# untitled.net
KiCad netlist of a schematic drawn in EAGLE
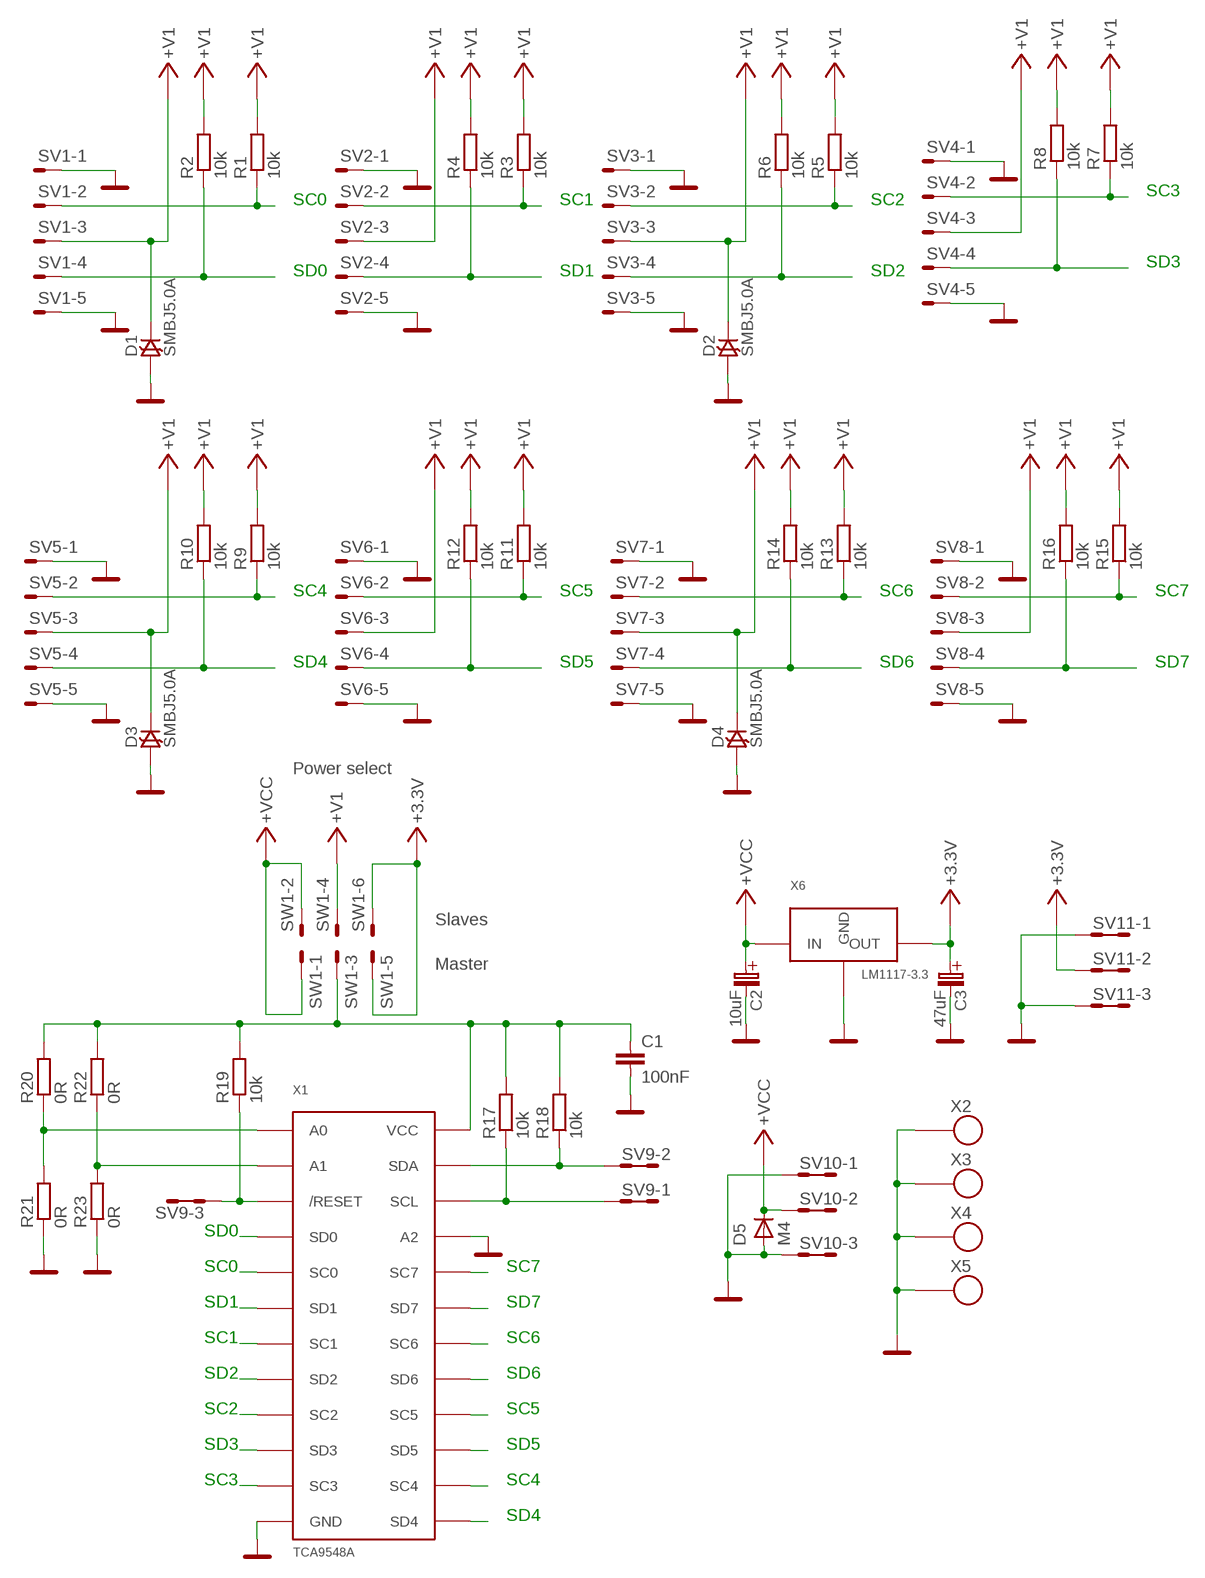
[diagram p0: schematic, sheet 1]

(export (version "E")
  (design (tool "Eeschema 10.0.6"))
  (components
    (comp (ref "C1")
      (value "100nF")
      (footprint "eagle-import:C0805")
      (libsource (lib "eagle-import") (part "C0805"))
    )
    (comp (ref "C2") (value "10uF") (footprint "eagle-import:B") (libsource (lib "eagle-import") (part "B")))
    (comp (ref "C3") (value "47uF") (footprint "eagle-import:C") (libsource (lib "eagle-import") (part "C")))
    (comp (ref "D1")
      (value "SMBJ5.0A")
      (footprint "eagle-import:SMA")
      (libsource (lib "eagle-import") (part "D-TRANSIL-SMA"))
    )
    (comp (ref "D2")
      (value "SMBJ5.0A")
      (footprint "eagle-import:SMA")
      (libsource (lib "eagle-import") (part "D-TRANSIL-SMA"))
    )
    (comp (ref "D3")
      (value "SMBJ5.0A")
      (footprint "eagle-import:SMA")
      (libsource (lib "eagle-import") (part "D-TRANSIL-SMA"))
    )
    (comp (ref "D4")
      (value "SMBJ5.0A")
      (footprint "eagle-import:SMA")
      (libsource (lib "eagle-import") (part "D-TRANSIL-SMA"))
    )
    (comp (ref "D5")
      (value "M4")
      (footprint "eagle-import:SMA")
      (libsource (lib "eagle-import") (part "D-OB.SMA"))
    )
    (comp (ref "R1")
      (value "10k")
      (footprint "eagle-import:0805")
      (libsource (lib "eagle-import") (part "R0805"))
    )
    (comp (ref "R2")
      (value "10k")
      (footprint "eagle-import:0805")
      (libsource (lib "eagle-import") (part "R0805"))
    )
    (comp (ref "R3")
      (value "10k")
      (footprint "eagle-import:0805")
      (libsource (lib "eagle-import") (part "R0805"))
    )
    (comp (ref "R4")
      (value "10k")
      (footprint "eagle-import:0805")
      (libsource (lib "eagle-import") (part "R0805"))
    )
    (comp (ref "R5")
      (value "10k")
      (footprint "eagle-import:0805")
      (libsource (lib "eagle-import") (part "R0805"))
    )
    (comp (ref "R6")
      (value "10k")
      (footprint "eagle-import:0805")
      (libsource (lib "eagle-import") (part "R0805"))
    )
    (comp (ref "R7")
      (value "10k")
      (footprint "eagle-import:0805")
      (libsource (lib "eagle-import") (part "R0805"))
    )
    (comp (ref "R8")
      (value "10k")
      (footprint "eagle-import:0805")
      (libsource (lib "eagle-import") (part "R0805"))
    )
    (comp (ref "R9")
      (value "10k")
      (footprint "eagle-import:0805")
      (libsource (lib "eagle-import") (part "R0805"))
    )
    (comp (ref "R10")
      (value "10k")
      (footprint "eagle-import:0805")
      (libsource (lib "eagle-import") (part "R0805"))
    )
    (comp (ref "R11")
      (value "10k")
      (footprint "eagle-import:0805")
      (libsource (lib "eagle-import") (part "R0805"))
    )
    (comp (ref "R12")
      (value "10k")
      (footprint "eagle-import:0805")
      (libsource (lib "eagle-import") (part "R0805"))
    )
    (comp (ref "R13")
      (value "10k")
      (footprint "eagle-import:0805")
      (libsource (lib "eagle-import") (part "R0805"))
    )
    (comp (ref "R14")
      (value "10k")
      (footprint "eagle-import:0805")
      (libsource (lib "eagle-import") (part "R0805"))
    )
    (comp (ref "R15")
      (value "10k")
      (footprint "eagle-import:0805")
      (libsource (lib "eagle-import") (part "R0805"))
    )
    (comp (ref "R16")
      (value "10k")
      (footprint "eagle-import:0805")
      (libsource (lib "eagle-import") (part "R0805"))
    )
    (comp (ref "R17")
      (value "10k")
      (footprint "eagle-import:0805")
      (libsource (lib "eagle-import") (part "R0805"))
    )
    (comp (ref "R18")
      (value "10k")
      (footprint "eagle-import:0805")
      (libsource (lib "eagle-import") (part "R0805"))
    )
    (comp (ref "R19")
      (value "10k")
      (footprint "eagle-import:0805")
      (libsource (lib "eagle-import") (part "R0805"))
    )
    (comp (ref "R20")
      (value "0R")
      (footprint "eagle-import:0805")
      (libsource (lib "eagle-import") (part "R0805"))
    )
    (comp (ref "R21")
      (value "0R")
      (footprint "eagle-import:0805")
      (libsource (lib "eagle-import") (part "R0805"))
    )
    (comp (ref "R22")
      (value "0R")
      (footprint "eagle-import:0805")
      (libsource (lib "eagle-import") (part "R0805"))
    )
    (comp (ref "R23")
      (value "0R")
      (footprint "eagle-import:0805")
      (libsource (lib "eagle-import") (part "R0805"))
    )
    (comp (ref "SV1")
      (value "MA05-1")
      (footprint "eagle-import:MA05-1")
      (libsource (lib "eagle-import") (part "MA05-1"))
    )
    (comp (ref "SV2")
      (value "MA05-1")
      (footprint "eagle-import:MA05-1")
      (libsource (lib "eagle-import") (part "MA05-1"))
    )
    (comp (ref "SV3")
      (value "MA05-1")
      (footprint "eagle-import:MA05-1")
      (libsource (lib "eagle-import") (part "MA05-1"))
    )
    (comp (ref "SV4")
      (value "MA05-1")
      (footprint "eagle-import:MA05-1")
      (libsource (lib "eagle-import") (part "MA05-1"))
    )
    (comp (ref "SV5")
      (value "MA05-1")
      (footprint "eagle-import:MA05-1")
      (libsource (lib "eagle-import") (part "MA05-1"))
    )
    (comp (ref "SV6")
      (value "MA05-1")
      (footprint "eagle-import:MA05-1")
      (libsource (lib "eagle-import") (part "MA05-1"))
    )
    (comp (ref "SV7")
      (value "MA05-1")
      (footprint "eagle-import:MA05-1")
      (libsource (lib "eagle-import") (part "MA05-1"))
    )
    (comp (ref "SV8")
      (value "MA05-1")
      (footprint "eagle-import:MA05-1")
      (libsource (lib "eagle-import") (part "MA05-1"))
    )
    (comp (ref "SV9")
      (value "MA03-2")
      (footprint "eagle-import:MA03-2")
      (libsource (lib "eagle-import") (part "MA03-2"))
    )
    (comp (ref "SV10")
      (value "MA03-2")
      (footprint "eagle-import:MA03-2")
      (libsource (lib "eagle-import") (part "MA03-2"))
    )
    (comp (ref "SV11")
      (value "MA03-2")
      (footprint "eagle-import:MA03-2")
      (libsource (lib "eagle-import") (part "MA03-2"))
    )
    (comp (ref "SW1")
      (value "MA03-3")
      (footprint "eagle-import:MA03-2")
      (libsource (lib "eagle-import") (part "MA03-3"))
    )
    (comp (ref "X1")
      (value "TCA9548A")
      (footprint "eagle-import:TSS0P24")
      (libsource (lib "eagle-import") (part "TCA9548A"))
    )
    (comp (ref "X2")
      (value "SROUB3M")
      (footprint "eagle-import:SROUB3M")
      (libsource (lib "eagle-import") (part "SROUB3M"))
    )
    (comp (ref "X3")
      (value "SROUB3M")
      (footprint "eagle-import:SROUB3M")
      (libsource (lib "eagle-import") (part "SROUB3M"))
    )
    (comp (ref "X4")
      (value "SROUB3M")
      (footprint "eagle-import:SROUB3M")
      (libsource (lib "eagle-import") (part "SROUB3M"))
    )
    (comp (ref "X5")
      (value "SROUB3M")
      (footprint "eagle-import:SROUB3M")
      (libsource (lib "eagle-import") (part "SROUB3M"))
    )
    (comp (ref "X6")
      (value "LM1117-3.3")
      (footprint "eagle-import:SOT223")
      (libsource (lib "eagle-import") (part "LM1117"))
    )
  )
  (nets
    (net (code "1") (name "+3.3V") (class "Default")
      (node (ref "C3") (pin "+") (pinfunction "C_EL+_+") (pintype "passive"))
      (node (ref "SV11") (pin "3") (pinfunction "K_3") (pintype "passive"))
      (node (ref "SV11") (pin "4") (pinfunction "K_4") (pintype "passive"))
      (node (ref "SW1") (pin "5") (pinfunction "P$1_5") (pintype "passive"))
      (node (ref "SW1") (pin "6") (pinfunction "P$1_6") (pintype "passive"))
      (node (ref "X6") (pin "2") (pinfunction "OUT_2") (pintype "bidirectional"))
      (node (ref "X6") (pin "4") (pinfunction "OUT_4") (pintype "bidirectional"))
    )
    (net (code "2") (name "+V1") (class "Default")
      (node (ref "D1") (pin "K") (pinfunction "K_K") (pintype "passive"))
      (node (ref "D2") (pin "K") (pinfunction "K_K") (pintype "passive"))
      (node (ref "D3") (pin "K") (pinfunction "K_K") (pintype "passive"))
      (node (ref "D4") (pin "K") (pinfunction "K_K") (pintype "passive"))
      (node (ref "R1") (pin "2") (pinfunction "2_2") (pintype "passive"))
      (node (ref "R10") (pin "2") (pinfunction "2_2") (pintype "passive"))
      (node (ref "R11") (pin "2") (pinfunction "2_2") (pintype "passive"))
      (node (ref "R12") (pin "2") (pinfunction "2_2") (pintype "passive"))
      (node (ref "R13") (pin "2") (pinfunction "2_2") (pintype "passive"))
      (node (ref "R14") (pin "2") (pinfunction "2_2") (pintype "passive"))
      (node (ref "R15") (pin "2") (pinfunction "2_2") (pintype "passive"))
      (node (ref "R16") (pin "2") (pinfunction "2_2") (pintype "passive"))
      (node (ref "R2") (pin "2") (pinfunction "2_2") (pintype "passive"))
      (node (ref "R3") (pin "2") (pinfunction "2_2") (pintype "passive"))
      (node (ref "R4") (pin "2") (pinfunction "2_2") (pintype "passive"))
      (node (ref "R5") (pin "2") (pinfunction "2_2") (pintype "passive"))
      (node (ref "R6") (pin "2") (pinfunction "2_2") (pintype "passive"))
      (node (ref "R7") (pin "2") (pinfunction "2_2") (pintype "passive"))
      (node (ref "R8") (pin "2") (pinfunction "2_2") (pintype "passive"))
      (node (ref "R9") (pin "2") (pinfunction "2_2") (pintype "passive"))
      (node (ref "SV1") (pin "3") (pinfunction "P$1_3") (pintype "passive"))
      (node (ref "SV2") (pin "3") (pinfunction "P$1_3") (pintype "passive"))
      (node (ref "SV3") (pin "3") (pinfunction "P$1_3") (pintype "passive"))
      (node (ref "SV4") (pin "3") (pinfunction "P$1_3") (pintype "passive"))
      (node (ref "SV5") (pin "3") (pinfunction "P$1_3") (pintype "passive"))
      (node (ref "SV6") (pin "3") (pinfunction "P$1_3") (pintype "passive"))
      (node (ref "SV7") (pin "3") (pinfunction "P$1_3") (pintype "passive"))
      (node (ref "SV8") (pin "3") (pinfunction "P$1_3") (pintype "passive"))
      (node (ref "SW1") (pin "4") (pinfunction "P$1_4") (pintype "passive"))
    )
    (net (code "3") (name "+VCC") (class "Default")
      (node (ref "C2") (pin "+") (pinfunction "C_EL+_+") (pintype "passive"))
      (node (ref "D5") (pin "K") (pinfunction "C_K") (pintype "passive"))
      (node (ref "SV10") (pin "3") (pinfunction "K_3") (pintype "passive"))
      (node (ref "SV10") (pin "4") (pinfunction "K_4") (pintype "passive"))
      (node (ref "SW1") (pin "1") (pinfunction "P$1_1") (pintype "passive"))
      (node (ref "SW1") (pin "2") (pinfunction "P$1_2") (pintype "passive"))
      (node (ref "X6") (pin "3") (pinfunction "IN_3") (pintype "bidirectional"))
    )
    (net (code "4") (name "/SC0") (class "Default")
      (node (ref "R1") (pin "1") (pinfunction "1_1") (pintype "passive"))
      (node (ref "SV1") (pin "2") (pinfunction "P$1_2") (pintype "passive"))
      (node (ref "X1") (pin "5") (pinfunction "SC0_5") (pintype "bidirectional"))
    )
    (net (code "5") (name "/SC1") (class "Default")
      (node (ref "R3") (pin "1") (pinfunction "1_1") (pintype "passive"))
      (node (ref "SV2") (pin "2") (pinfunction "P$1_2") (pintype "passive"))
      (node (ref "X1") (pin "7") (pinfunction "SC1_7") (pintype "bidirectional"))
    )
    (net (code "6") (name "/SC2") (class "Default")
      (node (ref "R5") (pin "1") (pinfunction "1_1") (pintype "passive"))
      (node (ref "SV3") (pin "2") (pinfunction "P$1_2") (pintype "passive"))
      (node (ref "X1") (pin "9") (pinfunction "SC2_9") (pintype "bidirectional"))
    )
    (net (code "7") (name "/SC3") (class "Default")
      (node (ref "R7") (pin "1") (pinfunction "1_1") (pintype "passive"))
      (node (ref "SV4") (pin "2") (pinfunction "P$1_2") (pintype "passive"))
      (node (ref "X1") (pin "11") (pinfunction "SC3_11") (pintype "bidirectional"))
    )
    (net (code "8") (name "/SC4") (class "Default")
      (node (ref "R9") (pin "1") (pinfunction "1_1") (pintype "passive"))
      (node (ref "SV5") (pin "2") (pinfunction "P$1_2") (pintype "passive"))
      (node (ref "X1") (pin "14") (pinfunction "SC4_14") (pintype "bidirectional"))
    )
    (net (code "9") (name "/SC5") (class "Default")
      (node (ref "R11") (pin "1") (pinfunction "1_1") (pintype "passive"))
      (node (ref "SV6") (pin "2") (pinfunction "P$1_2") (pintype "passive"))
      (node (ref "X1") (pin "16") (pinfunction "SC5_16") (pintype "bidirectional"))
    )
    (net (code "10") (name "/SC6") (class "Default")
      (node (ref "R13") (pin "1") (pinfunction "1_1") (pintype "passive"))
      (node (ref "SV7") (pin "2") (pinfunction "P$1_2") (pintype "passive"))
      (node (ref "X1") (pin "18") (pinfunction "SC6_18") (pintype "bidirectional"))
    )
    (net (code "11") (name "/SC7") (class "Default")
      (node (ref "R15") (pin "1") (pinfunction "1_1") (pintype "passive"))
      (node (ref "SV8") (pin "2") (pinfunction "P$1_2") (pintype "passive"))
      (node (ref "X1") (pin "20") (pinfunction "SC7_20") (pintype "bidirectional"))
    )
    (net (code "12") (name "/SD0") (class "Default")
      (node (ref "R2") (pin "1") (pinfunction "1_1") (pintype "passive"))
      (node (ref "SV1") (pin "4") (pinfunction "P$1_4") (pintype "passive"))
      (node (ref "X1") (pin "4") (pinfunction "SD0_4") (pintype "bidirectional"))
    )
    (net (code "13") (name "/SD1") (class "Default")
      (node (ref "R4") (pin "1") (pinfunction "1_1") (pintype "passive"))
      (node (ref "SV2") (pin "4") (pinfunction "P$1_4") (pintype "passive"))
      (node (ref "X1") (pin "6") (pinfunction "SD1_6") (pintype "bidirectional"))
    )
    (net (code "14") (name "/SD2") (class "Default")
      (node (ref "R6") (pin "1") (pinfunction "1_1") (pintype "passive"))
      (node (ref "SV3") (pin "4") (pinfunction "P$1_4") (pintype "passive"))
      (node (ref "X1") (pin "8") (pinfunction "SD2_8") (pintype "bidirectional"))
    )
    (net (code "15") (name "/SD3") (class "Default")
      (node (ref "R8") (pin "1") (pinfunction "1_1") (pintype "passive"))
      (node (ref "SV4") (pin "4") (pinfunction "P$1_4") (pintype "passive"))
      (node (ref "X1") (pin "10") (pinfunction "SD3_10") (pintype "bidirectional"))
    )
    (net (code "16") (name "/SD4") (class "Default")
      (node (ref "R10") (pin "1") (pinfunction "1_1") (pintype "passive"))
      (node (ref "SV5") (pin "4") (pinfunction "P$1_4") (pintype "passive"))
      (node (ref "X1") (pin "13") (pinfunction "SD4_13") (pintype "bidirectional"))
    )
    (net (code "17") (name "/SD5") (class "Default")
      (node (ref "R12") (pin "1") (pinfunction "1_1") (pintype "passive"))
      (node (ref "SV6") (pin "4") (pinfunction "P$1_4") (pintype "passive"))
      (node (ref "X1") (pin "15") (pinfunction "SD5_15") (pintype "bidirectional"))
    )
    (net (code "18") (name "/SD6") (class "Default")
      (node (ref "R14") (pin "1") (pinfunction "1_1") (pintype "passive"))
      (node (ref "SV7") (pin "4") (pinfunction "P$1_4") (pintype "passive"))
      (node (ref "X1") (pin "17") (pinfunction "SD6_17") (pintype "bidirectional"))
    )
    (net (code "19") (name "/SD7") (class "Default")
      (node (ref "R16") (pin "1") (pinfunction "1_1") (pintype "passive"))
      (node (ref "SV8") (pin "4") (pinfunction "P$1_4") (pintype "passive"))
      (node (ref "X1") (pin "19") (pinfunction "SD7_19") (pintype "bidirectional"))
    )
    (net (code "20") (name "GND") (class "Default")
      (node (ref "C1") (pin "2") (pinfunction "2_2") (pintype "passive"))
      (node (ref "C2") (pin "-") (pinfunction "C_EL-_-") (pintype "passive"))
      (node (ref "C3") (pin "-") (pinfunction "C_EL-_-") (pintype "passive"))
      (node (ref "D1") (pin "A") (pinfunction "A_A") (pintype "passive"))
      (node (ref "D2") (pin "A") (pinfunction "A_A") (pintype "passive"))
      (node (ref "D3") (pin "A") (pinfunction "A_A") (pintype "passive"))
      (node (ref "D4") (pin "A") (pinfunction "A_A") (pintype "passive"))
      (node (ref "D5") (pin "A") (pinfunction "A_A") (pintype "passive"))
      (node (ref "R21") (pin "1") (pinfunction "1_1") (pintype "passive"))
      (node (ref "R23") (pin "1") (pinfunction "1_1") (pintype "passive"))
      (node (ref "SV1") (pin "1") (pinfunction "P$1_1") (pintype "passive"))
      (node (ref "SV1") (pin "5") (pinfunction "P$1_5") (pintype "passive"))
      (node (ref "SV10") (pin "1") (pinfunction "K_1") (pintype "passive"))
      (node (ref "SV10") (pin "2") (pinfunction "K_2") (pintype "passive"))
      (node (ref "SV10") (pin "5") (pinfunction "K_5") (pintype "passive"))
      (node (ref "SV10") (pin "6") (pinfunction "K_6") (pintype "passive"))
      (node (ref "SV11") (pin "1") (pinfunction "K_1") (pintype "passive"))
      (node (ref "SV11") (pin "2") (pinfunction "K_2") (pintype "passive"))
      (node (ref "SV11") (pin "5") (pinfunction "K_5") (pintype "passive"))
      (node (ref "SV11") (pin "6") (pinfunction "K_6") (pintype "passive"))
      (node (ref "SV2") (pin "1") (pinfunction "P$1_1") (pintype "passive"))
      (node (ref "SV2") (pin "5") (pinfunction "P$1_5") (pintype "passive"))
      (node (ref "SV3") (pin "1") (pinfunction "P$1_1") (pintype "passive"))
      (node (ref "SV3") (pin "5") (pinfunction "P$1_5") (pintype "passive"))
      (node (ref "SV4") (pin "1") (pinfunction "P$1_1") (pintype "passive"))
      (node (ref "SV4") (pin "5") (pinfunction "P$1_5") (pintype "passive"))
      (node (ref "SV5") (pin "1") (pinfunction "P$1_1") (pintype "passive"))
      (node (ref "SV5") (pin "5") (pinfunction "P$1_5") (pintype "passive"))
      (node (ref "SV6") (pin "1") (pinfunction "P$1_1") (pintype "passive"))
      (node (ref "SV6") (pin "5") (pinfunction "P$1_5") (pintype "passive"))
      (node (ref "SV7") (pin "1") (pinfunction "P$1_1") (pintype "passive"))
      (node (ref "SV7") (pin "5") (pinfunction "P$1_5") (pintype "passive"))
      (node (ref "SV8") (pin "1") (pinfunction "P$1_1") (pintype "passive"))
      (node (ref "SV8") (pin "5") (pinfunction "P$1_5") (pintype "passive"))
      (node (ref "X1") (pin "12") (pinfunction "GND_12") (pintype "bidirectional"))
      (node (ref "X1") (pin "21") (pinfunction "A2_21") (pintype "bidirectional"))
      (node (ref "X2") (pin "P$1") (pinfunction "P$1_P$1") (pintype "bidirectional"))
      (node (ref "X3") (pin "P$1") (pinfunction "P$1_P$1") (pintype "bidirectional"))
      (node (ref "X4") (pin "P$1") (pinfunction "P$1_P$1") (pintype "bidirectional"))
      (node (ref "X5") (pin "P$1") (pinfunction "P$1_P$1") (pintype "bidirectional"))
      (node (ref "X6") (pin "1") (pinfunction "GND_1") (pintype "bidirectional"))
    )
    (net (code "21") (name "Net-(SW1C-P$1)") (class "Default")
      (node (ref "C1") (pin "1") (pinfunction "1_1") (pintype "passive"))
      (node (ref "R17") (pin "2") (pinfunction "2_2") (pintype "passive"))
      (node (ref "R18") (pin "2") (pinfunction "2_2") (pintype "passive"))
      (node (ref "R19") (pin "2") (pinfunction "2_2") (pintype "passive"))
      (node (ref "R20") (pin "2") (pinfunction "2_2") (pintype "passive"))
      (node (ref "R22") (pin "2") (pinfunction "2_2") (pintype "passive"))
      (node (ref "SW1") (pin "3") (pinfunction "P$1_3") (pintype "passive"))
      (node (ref "X1") (pin "24") (pinfunction "VCC_24") (pintype "bidirectional"))
    )
    (net (code "22") (name "Net-(X1-A0)") (class "Default")
      (node (ref "R20") (pin "1") (pinfunction "1_1") (pintype "passive"))
      (node (ref "R21") (pin "2") (pinfunction "2_2") (pintype "passive"))
      (node (ref "X1") (pin "1") (pinfunction "A0_1") (pintype "bidirectional"))
    )
    (net (code "23") (name "Net-(X1-A1)") (class "Default")
      (node (ref "R22") (pin "1") (pinfunction "1_1") (pintype "passive"))
      (node (ref "R23") (pin "2") (pinfunction "2_2") (pintype "passive"))
      (node (ref "X1") (pin "2") (pinfunction "A1_2") (pintype "bidirectional"))
    )
    (net (code "24") (name "Net-(X1-SCL)") (class "Default")
      (node (ref "R17") (pin "1") (pinfunction "1_1") (pintype "passive"))
      (node (ref "SV9") (pin "1") (pinfunction "K_1") (pintype "passive"))
      (node (ref "SV9") (pin "2") (pinfunction "K_2") (pintype "passive"))
      (node (ref "X1") (pin "22") (pinfunction "SCL_22") (pintype "bidirectional"))
    )
    (net (code "25") (name "Net-(X1-SDA)") (class "Default")
      (node (ref "R18") (pin "1") (pinfunction "1_1") (pintype "passive"))
      (node (ref "SV9") (pin "3") (pinfunction "K_3") (pintype "passive"))
      (node (ref "SV9") (pin "4") (pinfunction "K_4") (pintype "passive"))
      (node (ref "X1") (pin "23") (pinfunction "SDA_23") (pintype "bidirectional"))
    )
    (net (code "26") (name "Net-(X1-{slash}RESET)") (class "Default")
      (node (ref "R19") (pin "1") (pinfunction "1_1") (pintype "passive"))
      (node (ref "SV9") (pin "5") (pinfunction "K_5") (pintype "passive"))
      (node (ref "SV9") (pin "6") (pinfunction "K_6") (pintype "passive"))
      (node (ref "X1") (pin "3") (pinfunction "/RESET_3") (pintype "bidirectional"))
    )
  )
)
